# SMPS_1000mA_-_LM22672.net
KiCad netlist of a schematic drawn in Altium Designer
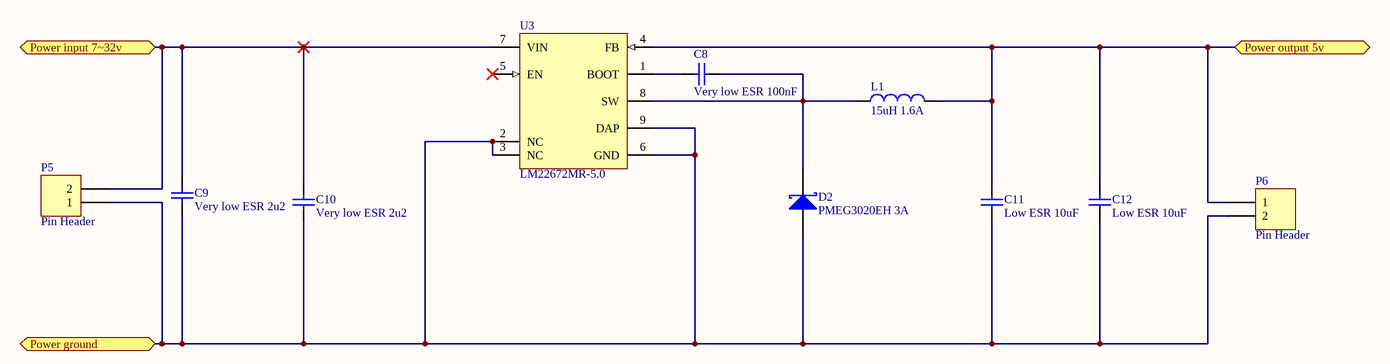
[diagram p0: SMPS 1000mA - LM22672.SchDoc]

(export (version "E")
  (design (tool "Eeschema 10.0.6"))
  (components
    (comp (ref "C8")
      (value "Very low ESR 100nF")
      (footprint "C0805")
      (fields
        (field (name "PART NUMBER") "0.01uF-0805-X7R")
        (field (name "VOLTAGE") "50V")
        (field (name "TOLERANCE") "0.1")
        (field (name "AUTHOR") "Willem Pietersz")
      )
      (libsource (lib "OurDb") (part "cap_NonPolar"))
    )
    (comp (ref "C9")
      (value "Very low ESR 2u2")
      (footprint "C1210")
      (fields
        (field (name "PART NUMBER") "2.2uF-1210-X7R")
        (field (name "VOLTAGE") "50V")
        (field (name "TOLERANCE") "0.1")
        (field (name "AUTHOR") "Willem Pietersz")
      )
      (libsource (lib "OurDb") (part "cap_NonPolar"))
    )
    (comp (ref "C10")
      (value "Very low ESR 2u2")
      (footprint "C1210")
      (fields
        (field (name "PART NUMBER") "2.2uF-1210-X7R")
        (field (name "VOLTAGE") "50V")
        (field (name "TOLERANCE") "0.1")
        (field (name "AUTHOR") "Willem Pietersz")
      )
      (libsource (lib "OurDb") (part "cap_NonPolar"))
    )
    (comp (ref "C11")
      (value "Low ESR 10uF")
      (footprint "C1210")
      (fields
        (field (name "PART NUMBER") "10uF-1210-X5R")
        (field (name "VOLTAGE") "10V")
        (field (name "TOLERANCE") "0.1")
        (field (name "AUTHOR") "Willem Pietersz")
      )
      (libsource (lib "OurDb") (part "cap_NonPolar"))
    )
    (comp (ref "C12")
      (value "Low ESR 10uF")
      (footprint "C1210")
      (fields
        (field (name "PART NUMBER") "10uF-1210-X5R")
        (field (name "VOLTAGE") "10V")
        (field (name "TOLERANCE") "0.1")
        (field (name "AUTHOR") "Willem Pietersz")
      )
      (libsource (lib "OurDb") (part "cap_NonPolar"))
    )
    (comp (ref "D2")
      (value "PMEG3020EH 3A")
      (footprint "SOD123F")
      (fields (field (name "PART NUMBER") "PMEG3020EH") (field (name "VOLTAGE") "30V"))
      (libsource (lib "OurDb") (part "SCHOTTKY"))
    )
    (comp (ref "L1")
      (value "15uH 1.6A")
      (footprint "Square_7.3x7.3x4.5")
      (description "Inductor")
      (fields (field (name "PART NUMBER") "15uH-Shield-1.6A-Wurth") (field (name "Comment") "inductor"))
      (libsource (lib "OurDb") (part "inductor"))
    )
    (comp (ref "P5")
      (value "Pin Header")
      (footprint "PH1x2_2.54")
      (description "Con1x2")
      (fields (field (name "PART NUMBER") "PH1x2") (field (name "AUTHOR") "Willy Pietersz"))
      (libsource (lib "") (part "Con1x2_1"))
    )
    (comp (ref "P6")
      (value "Pin Header")
      (footprint "PH1x2_2.54")
      (description "Con1x2")
      (fields (field (name "PART NUMBER") "PH1x2") (field (name "AUTHOR") "Willy Pietersz"))
      (libsource (lib "OurDb") (part "Con1x2"))
    )
    (comp (ref "U3")
      (value "LM22672MR-5.0")
      (footprint "MRA08B_N")
      (description "Power, 500mA SIMPLE SWITCHER, Step-Down Voltage Regulator with Precision Enable")
      (fields
        (field (name "PARTNUMBER") "LM22674MR-5.0")
        (field (name "MANUFACTURER") "National Semiconductor")
        (field (name "PUBLISHER") "Altium Limited")
      )
      (libsource (lib "AltiumDatabaseSelection") (part "LM22674MR-5.0"))
    )
  )
  (nets
    (net (code "1") (name "/Power ground") (class "Default")
      (node (ref "C10") (pin "1") (pinfunction "1_1") (pintype "passive"))
      (node (ref "C11") (pin "1") (pinfunction "1_1") (pintype "passive"))
      (node (ref "C12") (pin "1") (pinfunction "1_1") (pintype "passive"))
      (node (ref "C9") (pin "1") (pinfunction "1_1") (pintype "passive"))
      (node (ref "D2") (pin "1") (pinfunction "1_1") (pintype "passive"))
      (node (ref "P5") (pin "1") (pinfunction "1_1") (pintype "passive"))
      (node (ref "P6") (pin "2") (pinfunction "2_2") (pintype "passive"))
      (node (ref "U3") (pin "2") (pinfunction "NC_2") (pintype "passive"))
      (node (ref "U3") (pin "3") (pinfunction "NC_3") (pintype "passive"))
      (node (ref "U3") (pin "6") (pinfunction "GND_6") (pintype "power_in"))
      (node (ref "U3") (pin "9") (pinfunction "DAP_9") (pintype "power_in"))
    )
    (net (code "2") (name "/Power input 7~32v") (class "Default")
      (node (ref "C10") (pin "2") (pinfunction "2_2") (pintype "passive"))
      (node (ref "C9") (pin "2") (pinfunction "2_2") (pintype "passive"))
      (node (ref "P5") (pin "2") (pinfunction "2_2") (pintype "passive"))
      (node (ref "U3") (pin "7") (pinfunction "VIN_7") (pintype "power_in"))
    )
    (net (code "3") (name "/Power output 5v") (class "Default")
      (node (ref "C11") (pin "2") (pinfunction "2_2") (pintype "passive"))
      (node (ref "C12") (pin "2") (pinfunction "2_2") (pintype "passive"))
      (node (ref "L1") (pin "2") (pinfunction "2_2") (pintype "passive"))
      (node (ref "P6") (pin "1") (pinfunction "1_1") (pintype "passive"))
      (node (ref "U3") (pin "4") (pinfunction "FB_4") (pintype "input"))
    )
    (net (code "4") (name "Net-(U3-BOOT)") (class "Default")
      (node (ref "C8") (pin "1") (pinfunction "1_1") (pintype "passive"))
      (node (ref "U3") (pin "1") (pinfunction "BOOT_1") (pintype "passive"))
    )
    (net (code "5") (name "Net-(U3-SW)") (class "Default")
      (node (ref "C8") (pin "2") (pinfunction "2_2") (pintype "passive"))
      (node (ref "D2") (pin "2") (pinfunction "2_2") (pintype "passive"))
      (node (ref "L1") (pin "1") (pinfunction "1_1") (pintype "passive"))
      (node (ref "U3") (pin "8") (pinfunction "SW_8") (pintype "power_in"))
    )
    (net (code "6") (name "unconnected-(U3-EN-Pad5)") (class "Default")
      (node (ref "U3") (pin "5") (pinfunction "EN_5") (pintype "input+no_connect"))
    )
  )
)
